# openSX70_LENS_BELLOWS_V5_2-SEEED_2018022.net
KiCad netlist of a schematic drawn in EAGLE
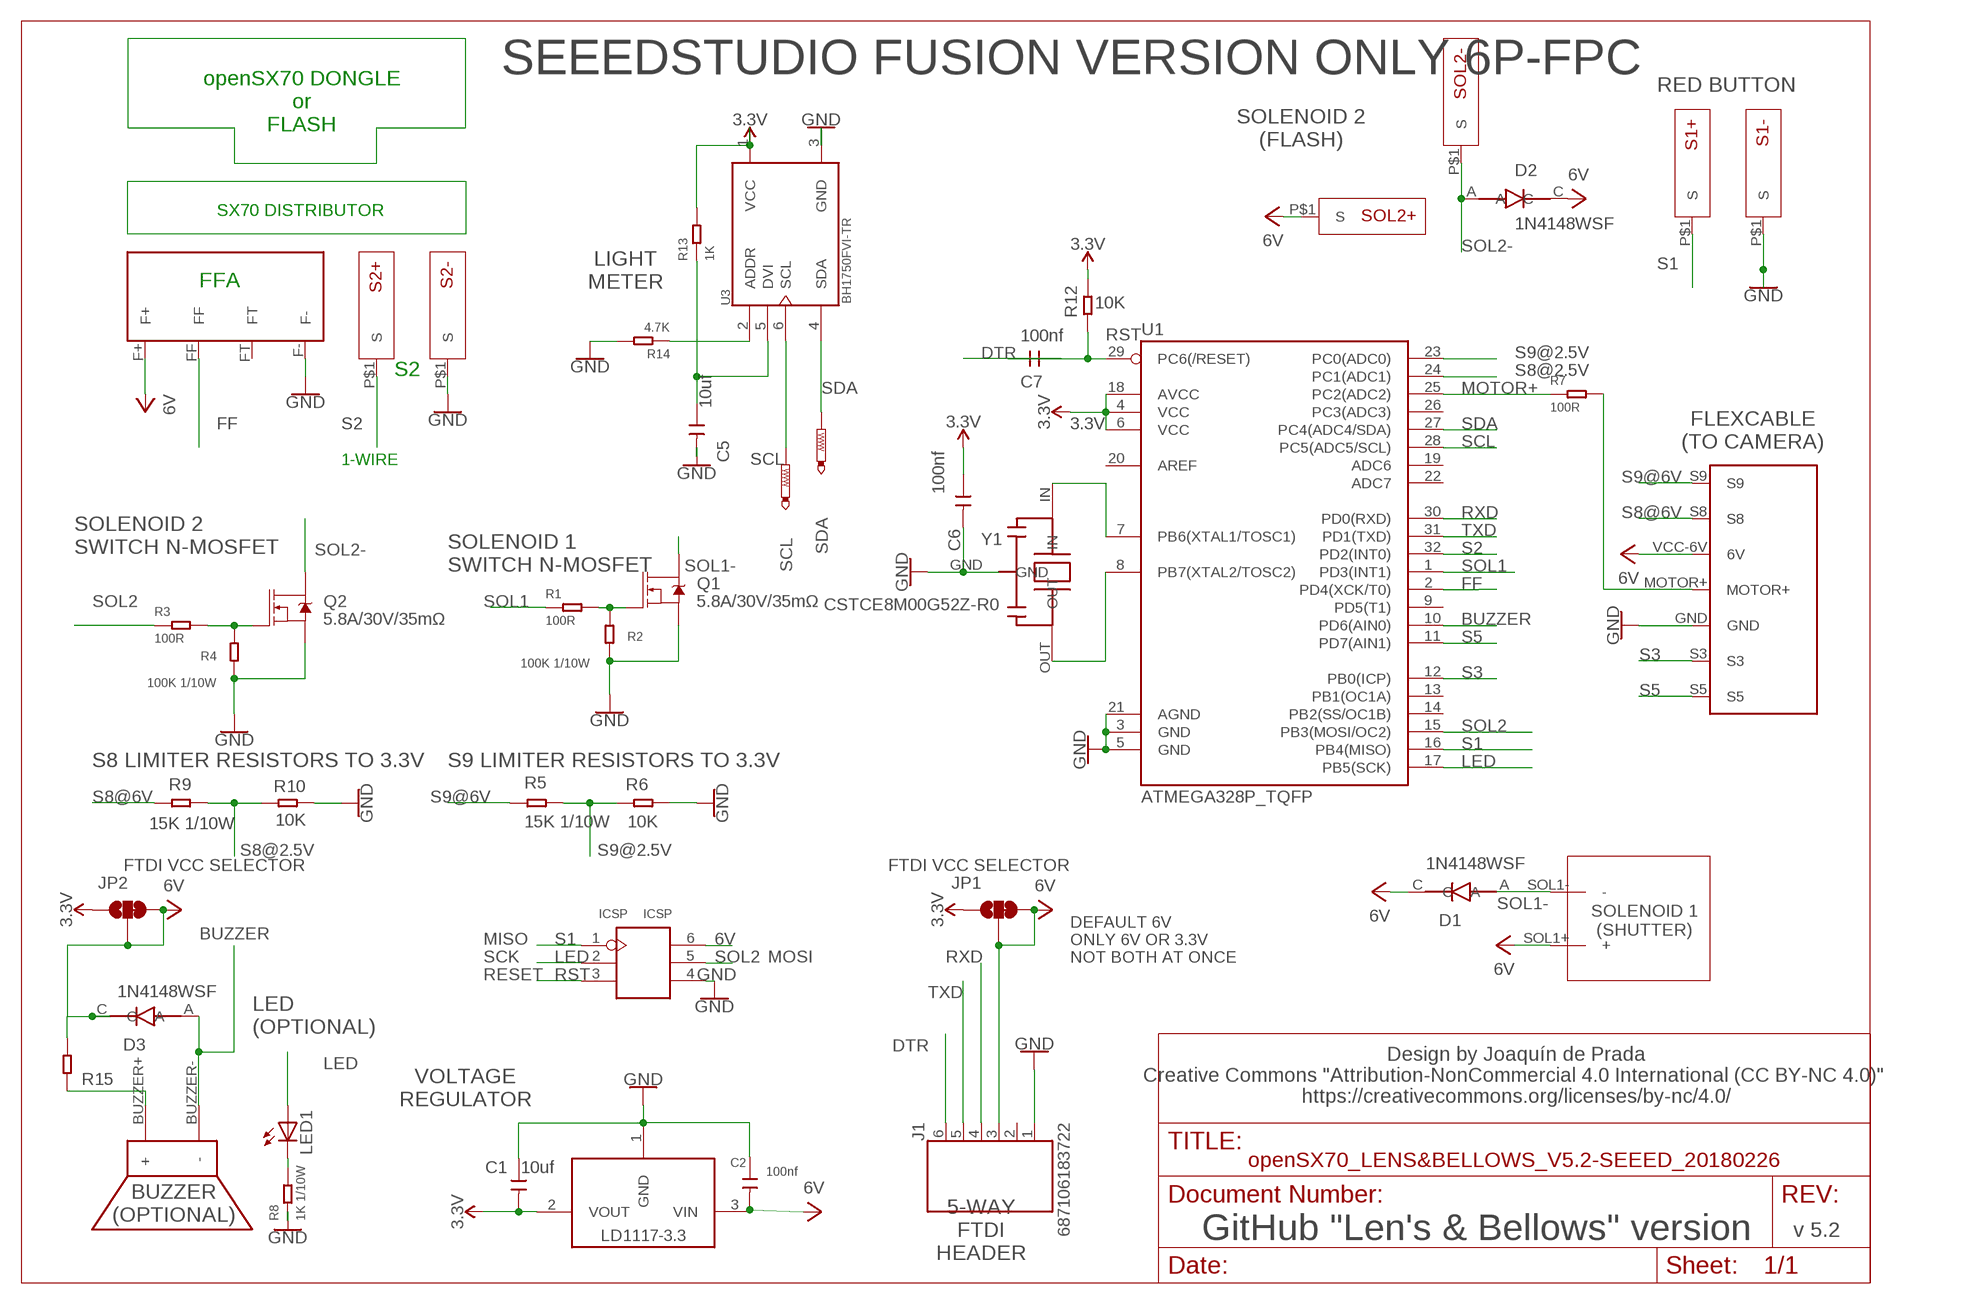
[diagram p0: schematic, sheet 1]

(export (version "E")
  (design (tool "Eeschema 10.0.6"))
  (components
    (comp (ref "C1")
      (value "10uf")
      (footprint "eagle-import:C0603")
      (fields (field (name "MPN") "CC0603KRX5R6BB106"))
      (libsource (lib "eagle-import") (part "CERAMIC-10UF-10V-10%-X5R(0603)"))
    )
    (comp (ref "C2")
      (value "100nf")
      (footprint "eagle-import:C0603")
      (fields (field (name "MPN") "CC0603KRX7R9BB104"))
      (libsource (lib "eagle-import") (part "CERAMIC-100NF-50V-10%-X7R(0603)"))
    )
    (comp (ref "C5")
      (value "10uf")
      (footprint "eagle-import:C0603")
      (fields (field (name "MPN") "CC0603KRX5R6BB106"))
      (libsource (lib "eagle-import") (part "CERAMIC-10UF-10V-10%-X5R(0603)"))
    )
    (comp (ref "C6")
      (value "100nf")
      (footprint "eagle-import:C0603")
      (fields (field (name "MPN") "CC0603KRX7R9BB104"))
      (libsource (lib "eagle-import") (part "CERAMIC-100NF-50V-10%-X7R(0603)"))
    )
    (comp (ref "C7")
      (value "100nf")
      (footprint "eagle-import:C0603")
      (fields (field (name "MPN") "CC0603KRX7R9BB104"))
      (libsource (lib "eagle-import") (part "CERAMIC-100NF-50V-10%-X7R(0603)"))
    )
    (comp (ref "D1")
      (value "1N4148WSF")
      (footprint "eagle-import:SODFL2512X100N")
      (fields (field (name "MANUFACTURER") "Fairchild Semiconductor"))
      (libsource (lib "eagle-import") (part "1N4148WS"))
    )
    (comp (ref "D2")
      (value "1N4148WSF")
      (footprint "eagle-import:SODFL2512X100N")
      (fields (field (name "MANUFACTURER") "Fairchild Semiconductor"))
      (libsource (lib "eagle-import") (part "1N4148WS"))
    )
    (comp (ref "D3")
      (value "1N4148WSF")
      (footprint "eagle-import:SODFL2512X100N")
      (fields (field (name "MANUFACTURER") "Fairchild Semiconductor"))
      (libsource (lib "eagle-import") (part "1N4148WS"))
    )
    (comp (ref "ICSP")
      (value "ICSP")
      (footprint "eagle-import:H2X3-2.54")
      (libsource (lib "eagle-import") (part "ICSP"))
    )
    (comp (ref "J1")
      (value "687106183722")
      (footprint "eagle-import:687106183722")
      (fields (field (name "MF") "Wurth Electronics"))
      (libsource (lib "eagle-import") (part "687106183722"))
    )
    (comp (ref "JP1")
      (value "FTDI VCC SELECTOR")
      (footprint "eagle-import:SMT-JUMPER_3_1-NC_TRACE_SILK")
      (libsource (lib "eagle-import") (part "JUMPER-SMT_3_1-NC_TRACE_SILK"))
    )
    (comp (ref "JP2")
      (value "FTDI VCC SELECTOR")
      (footprint "eagle-import:SMT-JUMPER_3_1-NC_TRACE_SILK")
      (libsource (lib "eagle-import") (part "JUMPER-SMT_3_1-NC_TRACE_SILK"))
    )
    (comp (ref "LD11172.5V")
      (value "LD1117 2.5V")
      (footprint "eagle-import:SOT223")
      (fields (field (name "MF") "Advanced Monolithic Systems") (field (name "MP") "AMS1117-5.0"))
      (libsource (lib "eagle-import") (part "LD1117-3.3"))
    )
    (comp (ref "LED1")
      (value "LEDCHIPLED_0805")
      (footprint "eagle-import:CHIPLED_0805")
      (libsource (lib "eagle-import") (part "LEDCHIPLED_0805"))
    )
    (comp (ref "Q1")
      (value "5.8A/30V/35mΩ")
      (footprint "eagle-import:SOT23-3")
      (libsource (lib "eagle-import") (part "MOSFET-NCH-AO3404A"))
    )
    (comp (ref "Q2")
      (value "5.8A/30V/35mΩ")
      (footprint "eagle-import:SOT23-3")
      (libsource (lib "eagle-import") (part "MOSFET-NCH-AO3404A"))
    )
    (comp (ref "R1")
      (value "100R")
      (footprint "eagle-import:R0603")
      (fields (field (name "MPN") "RC0603JR-07100RL"))
      (libsource (lib "eagle-import") (part "SMD-RES-100R-5%-1/10W(0603)"))
    )
    (comp (ref "R2")
      (value "100K 1/10W")
      (footprint "eagle-import:R0603")
      (fields (field (name "MPN") "RC0603JR-07100KL"))
      (libsource (lib "eagle-import") (part "SMD-RES-100K-5%-1/10W(0603)"))
    )
    (comp (ref "R3")
      (value "100R")
      (footprint "eagle-import:R0603")
      (fields (field (name "MPN") "RC0603JR-07100RL"))
      (libsource (lib "eagle-import") (part "SMD-RES-100R-5%-1/10W(0603)"))
    )
    (comp (ref "R4")
      (value "100K 1/10W")
      (footprint "eagle-import:R0603")
      (fields (field (name "MPN") "RC0603JR-07100KL"))
      (libsource (lib "eagle-import") (part "SMD-RES-100K-5%-1/10W(0603)"))
    )
    (comp (ref "R5")
      (value "15K 1/10W")
      (footprint "eagle-import:R0603")
      (fields (field (name "MPN") "RC0603FR-0715KL"))
      (libsource (lib "eagle-import") (part "SMD-RES-15K-1%-1/10W(0603)"))
    )
    (comp (ref "R6")
      (value "10K")
      (footprint "eagle-import:R0603")
      (fields (field (name "MPN") "RC0603FR-0710KL"))
      (libsource (lib "eagle-import") (part "SMD-RES-10K-1%-1/10W(0603)"))
    )
    (comp (ref "R7")
      (value "100R")
      (footprint "eagle-import:R0603")
      (fields (field (name "MPN") "RC0603JR-07100RL"))
      (libsource (lib "eagle-import") (part "SMD-RES-100R-5%-1/10W(0603)"))
    )
    (comp (ref "R8")
      (value "1K 1/10W")
      (footprint "eagle-import:R0603")
      (fields (field (name "MPN") "RC0603JR-071KL"))
      (libsource (lib "eagle-import") (part "SMD-RES-1K-5%-1/10W(0603)"))
    )
    (comp (ref "R9")
      (value "15K 1/10W")
      (footprint "eagle-import:R0603")
      (fields (field (name "MPN") "RC0603FR-0715KL"))
      (libsource (lib "eagle-import") (part "SMD-RES-15K-1%-1/10W(0603)"))
    )
    (comp (ref "R10")
      (value "10K")
      (footprint "eagle-import:R0603")
      (fields (field (name "MPN") "RC0603FR-0710KL"))
      (libsource (lib "eagle-import") (part "SMD-RES-10K-1%-1/10W(0603)"))
    )
    (comp (ref "R12")
      (value "10K")
      (footprint "eagle-import:R0603")
      (fields (field (name "MPN") "RC0603FR-0710KL"))
      (libsource (lib "eagle-import") (part "SMD-RES-10K-1%-1/10W(0603)"))
    )
    (comp (ref "R13")
      (value "1K")
      (footprint "eagle-import:R0603")
      (fields (field (name "MPN") "RC0603FR-071KL"))
      (libsource (lib "eagle-import") (part "SMD-RES-1K-1%-1/10W(0603)"))
    )
    (comp (ref "R14")
      (value "4.7K")
      (footprint "eagle-import:R0603")
      (fields (field (name "MPN") "RC0603JR-074K7L"))
      (libsource (lib "eagle-import") (part "SMD-RES-4.7K-5%-1/10W(0603)"))
    )
    (comp (ref "R15")
      (value "0R")
      (footprint "eagle-import:R0603")
      (fields (field (name "MPN") "RC0603JR-07100RL"))
      (libsource (lib "eagle-import") (part "SMD-RES-100R-5%-1/10W(0603)"))
    )
    (comp (ref "S1+")
      (value "SX70-S-PAD-NEW")
      (footprint "eagle-import:SX70-S-PAD2")
      (libsource (lib "eagle-import") (part "SX70-S-PAD-NEW"))
    )
    (comp (ref "S1-")
      (value "SX70-S-PAD-NEW")
      (footprint "eagle-import:SX70-S-PAD2")
      (libsource (lib "eagle-import") (part "SX70-S-PAD-NEW"))
    )
    (comp (ref "S2+")
      (value "SX70-S-PAD-NEW")
      (footprint "eagle-import:SX70-S-PAD2")
      (libsource (lib "eagle-import") (part "SX70-S-PAD-NEW"))
    )
    (comp (ref "S2-")
      (value "SX70-S-PAD-NEW")
      (footprint "eagle-import:SX70-S-PAD2")
      (libsource (lib "eagle-import") (part "SX70-S-PAD-NEW"))
    )
    (comp (ref "SCL")
      (value "PTR1TP08R")
      (footprint "eagle-import:TP08R")
      (libsource (lib "eagle-import") (part "PTR1TP08R"))
    )
    (comp (ref "SDA")
      (value "PTR1TP08R")
      (footprint "eagle-import:TP08R")
      (libsource (lib "eagle-import") (part "PTR1TP08R"))
    )
    (comp (ref "SOL1")
      (value "SX70-SOLENOID1-2PADS")
      (footprint "eagle-import:SX70-SOLENOID1-2")
      (libsource (lib "eagle-import") (part "SX70-SOLENOID1-2PADS"))
    )
    (comp (ref "SOL2+")
      (value "SX70-S-PAD-NEW")
      (footprint "eagle-import:SX70-S-PAD2")
      (libsource (lib "eagle-import") (part "SX70-S-PAD-NEW"))
    )
    (comp (ref "SOL2-")
      (value "SX70-S-PAD-NEW")
      (footprint "eagle-import:SX70-S-PAD2")
      (libsource (lib "eagle-import") (part "SX70-S-PAD-NEW"))
    )
    (comp (ref "U$1")
      (value "SX70-7-PAD")
      (footprint "eagle-import:SX70-7-PAD")
      (libsource (lib "eagle-import") (part "SX70-7-PAD"))
    )
    (comp (ref "U$2")
      (value "FFA")
      (footprint "eagle-import:FFA-PAD-PACKAGE")
      (libsource (lib "eagle-import") (part "SX70-FFA-PAD"))
    )
    (comp (ref "U$3")
      (value "CSET8-5G_V2")
      (footprint "eagle-import:CSET8-5G_PACKAGE")
      (libsource (lib "eagle-import") (part "CSET8-5G_V2"))
    )
    (comp (ref "U1")
      (value "ATMEGA328P_TQFP")
      (footprint "eagle-import:TQFP32-08")
      (libsource (lib "eagle-import") (part "ATMEGA328P_TQFP"))
    )
    (comp (ref "U3")
      (value "BH1750FVI-TR")
      (footprint "eagle-import:SOTFL50P300X75-6N")
      (fields (field (name "MF") "Rohm"))
      (libsource (lib "eagle-import") (part "BH1750FVI-TR"))
    )
    (comp (ref "Y1")
      (value "CSTCE8M00G52Z-R0")
      (footprint "eagle-import:CFP95P160X100-3N")
      (fields (field (name "MF") "Murata") (field (name "MP") "CSTCE16M0V53-R0"))
      (libsource (lib "eagle-import") (part "CSTCE16M0V53-R0"))
    )
  )
  (nets
    (net (code "1") (name "/BUZZER") (class "Default")
      (node (ref "D3") (pin "A") (pinfunction "A_A") (pintype "passive"))
      (node (ref "U$3") (pin "BUZZER-") (pinfunction "-_BUZZER-") (pintype "bidirectional"))
      (node (ref "U1") (pin "10") (pinfunction "PD6(AIN0)_10") (pintype "bidirectional"))
    )
    (net (code "2") (name "/DTR") (class "Default")
      (node (ref "C7") (pin "1") (pinfunction "1_1") (pintype "passive"))
      (node (ref "J1") (pin "6") (pinfunction "1_6") (pintype "passive"))
    )
    (net (code "3") (name "/FF") (class "Default")
      (node (ref "U$2") (pin "FF") (pinfunction "FF_FF") (pintype "bidirectional"))
      (node (ref "U1") (pin "2") (pinfunction "PD4(XCK/T0)_2") (pintype "bidirectional"))
    )
    (net (code "4") (name "/LED") (class "Default")
      (node (ref "ICSP") (pin "2") (pinfunction "SCK_2") (pintype "bidirectional"))
      (node (ref "LED1") (pin "A") (pinfunction "A_A") (pintype "passive"))
      (node (ref "U1") (pin "17") (pinfunction "PB5(SCK)_17") (pintype "bidirectional"))
    )
    (net (code "5") (name "/MOTOR+") (class "Default")
      (node (ref "R7") (pin "1") (pinfunction "1_1") (pintype "passive"))
      (node (ref "U1") (pin "25") (pinfunction "PC2(ADC2)_25") (pintype "bidirectional"))
    )
    (net (code "6") (name "/RST") (class "Default")
      (node (ref "C7") (pin "2") (pinfunction "2_2") (pintype "passive"))
      (node (ref "ICSP") (pin "3") (pinfunction "RST_3") (pintype "bidirectional"))
      (node (ref "R12") (pin "1") (pinfunction "1_1") (pintype "passive"))
      (node (ref "U1") (pin "29") (pinfunction "PC6(/RESET)_29") (pintype "bidirectional"))
    )
    (net (code "7") (name "/RXD") (class "Default")
      (node (ref "J1") (pin "4") (pinfunction "3_4") (pintype "passive"))
      (node (ref "U1") (pin "30") (pinfunction "PD0(RXD)_30") (pintype "bidirectional"))
    )
    (net (code "8") (name "/S1") (class "Default")
      (node (ref "ICSP") (pin "1") (pinfunction "MISO_1") (pintype "bidirectional"))
      (node (ref "S1+") (pin "P$1") (pinfunction "S_P$1") (pintype "bidirectional"))
      (node (ref "U1") (pin "16") (pinfunction "PB4(MISO)_16") (pintype "bidirectional"))
    )
    (net (code "9") (name "/S2") (class "Default")
      (node (ref "S2+") (pin "P$1") (pinfunction "S_P$1") (pintype "bidirectional"))
      (node (ref "U1") (pin "32") (pinfunction "PD2(INT0)_32") (pintype "bidirectional"))
    )
    (net (code "10") (name "/S3") (class "Default")
      (node (ref "U$1") (pin "S3") (pinfunction "S3_S3") (pintype "bidirectional"))
      (node (ref "U1") (pin "12") (pinfunction "PB0(ICP)_12") (pintype "bidirectional"))
    )
    (net (code "11") (name "/S5") (class "Default")
      (node (ref "U$1") (pin "S5") (pinfunction "S5_S5") (pintype "bidirectional"))
      (node (ref "U1") (pin "11") (pinfunction "PD7(AIN1)_11") (pintype "bidirectional"))
    )
    (net (code "12") (name "/S8@2.5V") (class "Default")
      (node (ref "R10") (pin "1") (pinfunction "1_1") (pintype "passive"))
      (node (ref "R9") (pin "2") (pinfunction "2_2") (pintype "passive"))
      (node (ref "U1") (pin "24") (pinfunction "PC1(ADC1)_24") (pintype "bidirectional"))
    )
    (net (code "13") (name "/S8@6V") (class "Default")
      (node (ref "R9") (pin "1") (pinfunction "1_1") (pintype "passive"))
      (node (ref "U$1") (pin "S8") (pinfunction "S8_S8") (pintype "bidirectional"))
    )
    (net (code "14") (name "/S9@2.5V") (class "Default")
      (node (ref "R5") (pin "2") (pinfunction "2_2") (pintype "passive"))
      (node (ref "R6") (pin "1") (pinfunction "1_1") (pintype "passive"))
      (node (ref "U1") (pin "23") (pinfunction "PC0(ADC0)_23") (pintype "bidirectional"))
    )
    (net (code "15") (name "/S9@6V") (class "Default")
      (node (ref "R5") (pin "1") (pinfunction "1_1") (pintype "passive"))
      (node (ref "U$1") (pin "S9") (pinfunction "S9_S9") (pintype "bidirectional"))
    )
    (net (code "16") (name "/SCL") (class "Default")
      (node (ref "SCL") (pin "TP") (pinfunction "TP_TP") (pintype "input"))
      (node (ref "U1") (pin "28") (pinfunction "PC5(ADC5/SCL)_28") (pintype "bidirectional"))
      (node (ref "U3") (pin "6") (pinfunction "SCL_6") (pintype "input"))
    )
    (net (code "17") (name "/SDA") (class "Default")
      (node (ref "SDA") (pin "TP") (pinfunction "TP_TP") (pintype "input"))
      (node (ref "U1") (pin "27") (pinfunction "PC4(ADC4/SDA)_27") (pintype "bidirectional"))
      (node (ref "U3") (pin "4") (pinfunction "SDA_4") (pintype "bidirectional"))
    )
    (net (code "18") (name "/SOL1") (class "Default")
      (node (ref "R1") (pin "1") (pinfunction "1_1") (pintype "passive"))
      (node (ref "U1") (pin "1") (pinfunction "PD3(INT1)_1") (pintype "bidirectional"))
    )
    (net (code "19") (name "/SOL1-") (class "Default")
      (node (ref "D1") (pin "A") (pinfunction "A_A") (pintype "passive"))
      (node (ref "Q1") (pin "3") (pinfunction "D_3") (pintype "bidirectional"))
      (node (ref "SOL1") (pin "SOL1-") (pinfunction "-_SOL1-") (pintype "bidirectional"))
    )
    (net (code "20") (name "/SOL2") (class "Default")
      (node (ref "ICSP") (pin "5") (pinfunction "MOSI_5") (pintype "bidirectional"))
      (node (ref "R3") (pin "1") (pinfunction "1_1") (pintype "passive"))
      (node (ref "U1") (pin "15") (pinfunction "PB3(MOSI/OC2)_15") (pintype "bidirectional"))
    )
    (net (code "21") (name "/SOL2-") (class "Default")
      (node (ref "D2") (pin "A") (pinfunction "A_A") (pintype "passive"))
      (node (ref "Q2") (pin "3") (pinfunction "D_3") (pintype "bidirectional"))
      (node (ref "SOL2-") (pin "P$1") (pinfunction "S_P$1") (pintype "bidirectional"))
    )
    (net (code "22") (name "/TXD") (class "Default")
      (node (ref "J1") (pin "5") (pinfunction "2_5") (pintype "passive"))
      (node (ref "U1") (pin "31") (pinfunction "PD1(TXD)_31") (pintype "bidirectional"))
    )
    (net (code "23") (name "3.3V") (class "Default")
      (node (ref "C1") (pin "2") (pinfunction "2_2") (pintype "passive"))
      (node (ref "C6") (pin "1") (pinfunction "1_1") (pintype "passive"))
      (node (ref "JP1") (pin "1") (pinfunction "1_1") (pintype "passive"))
      (node (ref "JP2") (pin "1") (pinfunction "1_1") (pintype "passive"))
      (node (ref "LD11172.5V") (pin "2") (pinfunction "VOUT_2") (pintype "bidirectional"))
      (node (ref "R12") (pin "2") (pinfunction "2_2") (pintype "passive"))
      (node (ref "R13") (pin "2") (pinfunction "2_2") (pintype "passive"))
      (node (ref "U1") (pin "18") (pinfunction "AVCC_18") (pintype "bidirectional"))
      (node (ref "U1") (pin "4") (pinfunction "VCC_4") (pintype "bidirectional"))
      (node (ref "U1") (pin "6") (pinfunction "VCC_6") (pintype "bidirectional"))
      (node (ref "U3") (pin "1") (pinfunction "VCC_1") (pintype "power_in"))
    )
    (net (code "24") (name "6V") (class "Default")
      (node (ref "C2") (pin "2") (pinfunction "2_2") (pintype "passive"))
      (node (ref "D1") (pin "C") (pinfunction "C_C") (pintype "passive"))
      (node (ref "D2") (pin "C") (pinfunction "C_C") (pintype "passive"))
      (node (ref "D3") (pin "C") (pinfunction "C_C") (pintype "passive"))
      (node (ref "ICSP") (pin "6") (pinfunction "VCC_6") (pintype "bidirectional"))
      (node (ref "J1") (pin "3") (pinfunction "4_3") (pintype "passive"))
      (node (ref "JP1") (pin "2") (pinfunction "2_2") (pintype "passive"))
      (node (ref "JP1") (pin "3") (pinfunction "3_3") (pintype "passive"))
      (node (ref "JP2") (pin "2") (pinfunction "2_2") (pintype "passive"))
      (node (ref "JP2") (pin "3") (pinfunction "3_3") (pintype "passive"))
      (node (ref "LD11172.5V") (pin "3") (pinfunction "VIN_3") (pintype "bidirectional"))
      (node (ref "R15") (pin "2") (pinfunction "2_2") (pintype "passive"))
      (node (ref "SOL1") (pin "SOL1+") (pinfunction "+_SOL1+") (pintype "bidirectional"))
      (node (ref "SOL2+") (pin "P$1") (pinfunction "S_P$1") (pintype "bidirectional"))
      (node (ref "U$1") (pin "VCC-6V") (pinfunction "6V_VCC-6V") (pintype "bidirectional"))
      (node (ref "U$2") (pin "F+") (pinfunction "F+_F+") (pintype "bidirectional"))
    )
    (net (code "25") (name "GND") (class "Default")
      (node (ref "C1") (pin "1") (pinfunction "1_1") (pintype "passive"))
      (node (ref "C2") (pin "1") (pinfunction "1_1") (pintype "passive"))
      (node (ref "C5") (pin "2") (pinfunction "2_2") (pintype "passive"))
      (node (ref "C6") (pin "2") (pinfunction "2_2") (pintype "passive"))
      (node (ref "ICSP") (pin "4") (pinfunction "GND_4") (pintype "bidirectional"))
      (node (ref "J1") (pin "1") (pinfunction "6_1") (pintype "passive"))
      (node (ref "LD11172.5V") (pin "1") (pinfunction "GND_1") (pintype "bidirectional"))
      (node (ref "Q1") (pin "2") (pinfunction "S_2") (pintype "bidirectional"))
      (node (ref "Q2") (pin "2") (pinfunction "S_2") (pintype "bidirectional"))
      (node (ref "R10") (pin "2") (pinfunction "2_2") (pintype "passive"))
      (node (ref "R14") (pin "2") (pinfunction "2_2") (pintype "passive"))
      (node (ref "R2") (pin "1") (pinfunction "1_1") (pintype "passive"))
      (node (ref "R4") (pin "1") (pinfunction "1_1") (pintype "passive"))
      (node (ref "R6") (pin "2") (pinfunction "2_2") (pintype "passive"))
      (node (ref "R8") (pin "1") (pinfunction "1_1") (pintype "passive"))
      (node (ref "S1-") (pin "P$1") (pinfunction "S_P$1") (pintype "bidirectional"))
      (node (ref "S2-") (pin "P$1") (pinfunction "S_P$1") (pintype "bidirectional"))
      (node (ref "U$1") (pin "GND") (pinfunction "GND_GND") (pintype "bidirectional"))
      (node (ref "U$2") (pin "F-") (pinfunction "F-_F-") (pintype "bidirectional"))
      (node (ref "U1") (pin "21") (pinfunction "AGND_21") (pintype "bidirectional"))
      (node (ref "U1") (pin "3") (pinfunction "GND_3") (pintype "bidirectional"))
      (node (ref "U1") (pin "5") (pinfunction "GND_5") (pintype "bidirectional"))
      (node (ref "U3") (pin "3") (pinfunction "GND_3") (pintype "power_in"))
      (node (ref "Y1") (pin "GND") (pinfunction "GND_GND") (pintype "passive"))
    )
    (net (code "26") (name "Net-(LED1-PadC)") (class "Default")
      (node (ref "LED1") (pin "C") (pinfunction "C_C") (pintype "passive"))
      (node (ref "R8") (pin "2") (pinfunction "2_2") (pintype "passive"))
    )
    (net (code "27") (name "Net-(Q1-G)") (class "Default")
      (node (ref "Q1") (pin "1") (pinfunction "G_1") (pintype "bidirectional"))
      (node (ref "R1") (pin "2") (pinfunction "2_2") (pintype "passive"))
      (node (ref "R2") (pin "2") (pinfunction "2_2") (pintype "passive"))
    )
    (net (code "28") (name "Net-(Q2-G)") (class "Default")
      (node (ref "Q2") (pin "1") (pinfunction "G_1") (pintype "bidirectional"))
      (node (ref "R3") (pin "2") (pinfunction "2_2") (pintype "passive"))
      (node (ref "R4") (pin "2") (pinfunction "2_2") (pintype "passive"))
    )
    (net (code "29") (name "Net-(R7-Pad2)") (class "Default")
      (node (ref "R7") (pin "2") (pinfunction "2_2") (pintype "passive"))
      (node (ref "U$1") (pin "MOTOR+") (pinfunction "MOTOR+_MOTOR+") (pintype "bidirectional"))
    )
    (net (code "30") (name "Net-(U$3-+)") (class "Default")
      (node (ref "R15") (pin "1") (pinfunction "1_1") (pintype "passive"))
      (node (ref "U$3") (pin "BUZZER+") (pinfunction "+_BUZZER+") (pintype "bidirectional"))
    )
    (net (code "31") (name "Net-(U1-PB6(XTAL1{slash}TOSC1))") (class "Default")
      (node (ref "U1") (pin "7") (pinfunction "PB6(XTAL1/TOSC1)_7") (pintype "bidirectional"))
      (node (ref "Y1") (pin "IN") (pinfunction "IN_IN") (pintype "input"))
    )
    (net (code "32") (name "Net-(U1-PB7(XTAL2{slash}TOSC2))") (class "Default")
      (node (ref "U1") (pin "8") (pinfunction "PB7(XTAL2/TOSC2)_8") (pintype "bidirectional"))
      (node (ref "Y1") (pin "OUT") (pinfunction "OUT_OUT") (pintype "output"))
    )
    (net (code "33") (name "Net-(U3-ADDR)") (class "Default")
      (node (ref "R14") (pin "1") (pinfunction "1_1") (pintype "passive"))
      (node (ref "U3") (pin "2") (pinfunction "ADDR_2") (pintype "input"))
    )
    (net (code "34") (name "Net-(U3-DVI)") (class "Default")
      (node (ref "C5") (pin "1") (pinfunction "1_1") (pintype "passive"))
      (node (ref "R13") (pin "1") (pinfunction "1_1") (pintype "passive"))
      (node (ref "U3") (pin "5") (pinfunction "DVI_5") (pintype "input"))
    )
    (net (code "35") (name "unconnected-(J1-5-Pad2)") (class "Default")
      (node (ref "J1") (pin "2") (pinfunction "5_2") (pintype "passive"))
    )
    (net (code "36") (name "unconnected-(U$2-PadFT)") (class "Default")
      (node (ref "U$2") (pin "FT") (pinfunction "FT_FT") (pintype "bidirectional"))
    )
    (net (code "37") (name "unconnected-(U1-ADC6-Pad19)") (class "Default")
      (node (ref "U1") (pin "19") (pinfunction "ADC6_19") (pintype "bidirectional"))
    )
    (net (code "38") (name "unconnected-(U1-ADC7-Pad22)") (class "Default")
      (node (ref "U1") (pin "22") (pinfunction "ADC7_22") (pintype "bidirectional"))
    )
    (net (code "39") (name "unconnected-(U1-AREF-Pad20)") (class "Default")
      (node (ref "U1") (pin "20") (pinfunction "AREF_20") (pintype "bidirectional"))
    )
    (net (code "40") (name "unconnected-(U1-PB1(OC1A)-Pad13)") (class "Default")
      (node (ref "U1") (pin "13") (pinfunction "PB1(OC1A)_13") (pintype "bidirectional"))
    )
    (net (code "41") (name "unconnected-(U1-PB2(SS{slash}OC1B)-Pad14)") (class "Default")
      (node (ref "U1") (pin "14") (pinfunction "PB2(SS/OC1B)_14") (pintype "bidirectional"))
    )
    (net (code "42") (name "unconnected-(U1-PC3(ADC3)-Pad26)") (class "Default")
      (node (ref "U1") (pin "26") (pinfunction "PC3(ADC3)_26") (pintype "bidirectional"))
    )
    (net (code "43") (name "unconnected-(U1-PD5(T1)-Pad9)") (class "Default")
      (node (ref "U1") (pin "9") (pinfunction "PD5(T1)_9") (pintype "bidirectional"))
    )
  )
)
